# Sheet5.net
KiCad netlist of a schematic drawn in Altium Designer
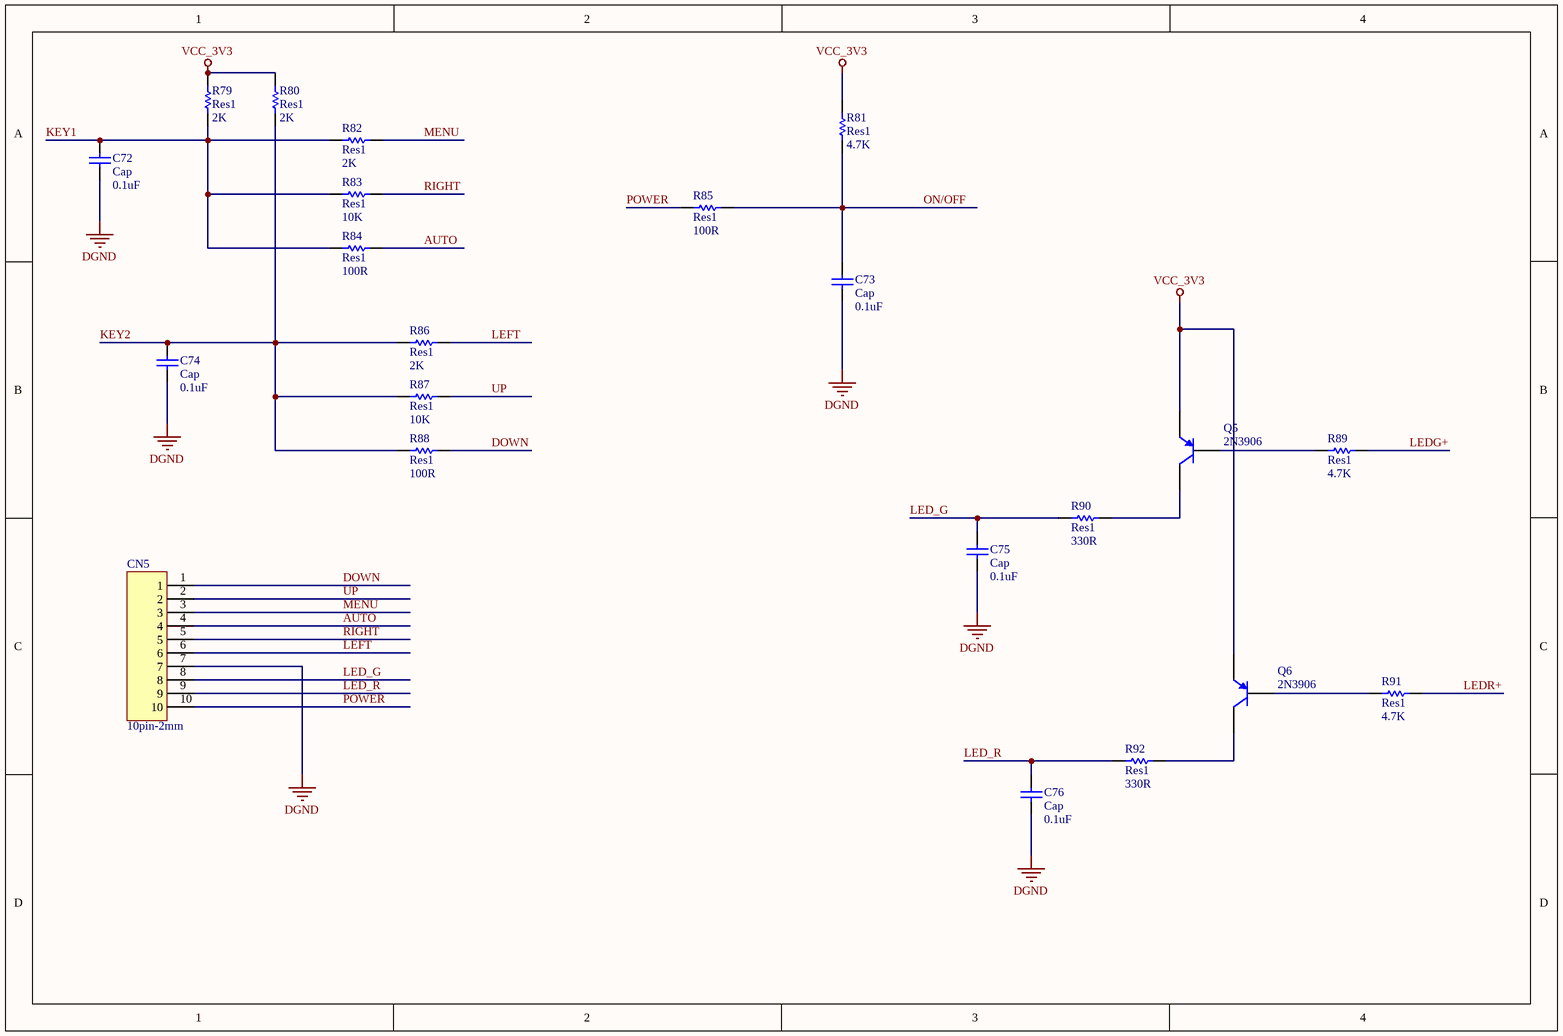
[diagram p0: Sheet5.SchDoc]

(export (version "E")
  (design (tool "Eeschema 10.0.6"))
  (components
    (comp (ref "C72")
      (value "Cap")
      (footprint "C-0402")
      (description "Capacitor")
      (fields (field (name "ALTIUM_VALUE") "0.1uF") (field (name "PUBLISHER") "Altium Limited"))
      (libsource (lib "Miscellaneous Devices") (part "Cap"))
    )
    (comp (ref "C73")
      (value "Cap")
      (footprint "C-0402")
      (description "Capacitor")
      (fields (field (name "ALTIUM_VALUE") "0.1uF") (field (name "PUBLISHER") "Altium Limited"))
      (libsource (lib "Miscellaneous Devices") (part "Cap"))
    )
    (comp (ref "C74")
      (value "Cap")
      (footprint "C-0402")
      (description "Capacitor")
      (fields (field (name "ALTIUM_VALUE") "0.1uF") (field (name "PUBLISHER") "Altium Limited"))
      (libsource (lib "Miscellaneous Devices") (part "Cap"))
    )
    (comp (ref "C75")
      (value "Cap")
      (footprint "C-0402")
      (description "Capacitor")
      (fields (field (name "ALTIUM_VALUE") "0.1uF") (field (name "PUBLISHER") "Altium Limited"))
      (libsource (lib "Miscellaneous Devices") (part "Cap"))
    )
    (comp (ref "C76")
      (value "Cap")
      (footprint "C-0402")
      (description "Capacitor")
      (fields (field (name "ALTIUM_VALUE") "0.1uF") (field (name "PUBLISHER") "Altium Limited"))
      (libsource (lib "Miscellaneous Devices") (part "Cap"))
    )
    (comp (ref "CN5") (value "10pin-2mm") (footprint "JP-10") (libsource (lib "SCHLIB") (part "10pin-2mm")))
    (comp (ref "Q5")
      (value "2N3906")
      (footprint "Q-SOT23")
      (description "PNP General Purpose Amplifier")
      (fields (field (name "PUBLISHER") "Altium Limited"))
      (libsource (lib "Miscellaneous Devices") (part "2N3906"))
    )
    (comp (ref "Q6")
      (value "2N3906")
      (footprint "Q-SOT23")
      (description "PNP General Purpose Amplifier")
      (fields (field (name "PUBLISHER") "Altium Limited"))
      (libsource (lib "Miscellaneous Devices") (part "2N3906"))
    )
    (comp (ref "R79")
      (value "Res1")
      (footprint "R-0603")
      (description "Resistor")
      (fields (field (name "ALTIUM_VALUE") "2K") (field (name "PUBLISHER") "Altium Limited"))
      (libsource (lib "Miscellaneous Devices") (part "Res1"))
    )
    (comp (ref "R80")
      (value "Res1")
      (footprint "R-0603")
      (description "Resistor")
      (fields (field (name "ALTIUM_VALUE") "2K") (field (name "PUBLISHER") "Altium Limited"))
      (libsource (lib "Miscellaneous Devices") (part "Res1"))
    )
    (comp (ref "R81")
      (value "Res1")
      (footprint "R-0603")
      (description "Resistor")
      (fields (field (name "ALTIUM_VALUE") "4.7K") (field (name "PUBLISHER") "Altium Limited"))
      (libsource (lib "Miscellaneous Devices") (part "Res1"))
    )
    (comp (ref "R82")
      (value "Res1")
      (footprint "R-0603")
      (description "Resistor")
      (fields (field (name "ALTIUM_VALUE") "2K") (field (name "PUBLISHER") "Altium Limited"))
      (libsource (lib "Miscellaneous Devices") (part "Res1"))
    )
    (comp (ref "R83")
      (value "Res1")
      (footprint "R-0603")
      (description "Resistor")
      (fields (field (name "ALTIUM_VALUE") "10K") (field (name "PUBLISHER") "Altium Limited"))
      (libsource (lib "Miscellaneous Devices") (part "Res1"))
    )
    (comp (ref "R84")
      (value "Res1")
      (footprint "R-0603")
      (description "Resistor")
      (fields (field (name "ALTIUM_VALUE") "100R") (field (name "PUBLISHER") "Altium Limited"))
      (libsource (lib "Miscellaneous Devices") (part "Res1"))
    )
    (comp (ref "R85")
      (value "Res1")
      (footprint "R-0603")
      (description "Resistor")
      (fields (field (name "ALTIUM_VALUE") "100R") (field (name "PUBLISHER") "Altium Limited"))
      (libsource (lib "Miscellaneous Devices") (part "Res1"))
    )
    (comp (ref "R86")
      (value "Res1")
      (footprint "R-0603")
      (description "Resistor")
      (fields (field (name "ALTIUM_VALUE") "2K") (field (name "PUBLISHER") "Altium Limited"))
      (libsource (lib "Miscellaneous Devices") (part "Res1"))
    )
    (comp (ref "R87")
      (value "Res1")
      (footprint "R-0603")
      (description "Resistor")
      (fields (field (name "ALTIUM_VALUE") "10K") (field (name "PUBLISHER") "Altium Limited"))
      (libsource (lib "Miscellaneous Devices") (part "Res1"))
    )
    (comp (ref "R88")
      (value "Res1")
      (footprint "R-0603")
      (description "Resistor")
      (fields (field (name "ALTIUM_VALUE") "100R") (field (name "PUBLISHER") "Altium Limited"))
      (libsource (lib "Miscellaneous Devices") (part "Res1"))
    )
    (comp (ref "R89")
      (value "Res1")
      (footprint "R-0603")
      (description "Resistor")
      (fields (field (name "ALTIUM_VALUE") "4.7K") (field (name "PUBLISHER") "Altium Limited"))
      (libsource (lib "Miscellaneous Devices") (part "Res1"))
    )
    (comp (ref "R90")
      (value "Res1")
      (footprint "R-0603")
      (description "Resistor")
      (fields (field (name "ALTIUM_VALUE") "330R") (field (name "PUBLISHER") "Altium Limited"))
      (libsource (lib "Miscellaneous Devices") (part "Res1"))
    )
    (comp (ref "R91")
      (value "Res1")
      (footprint "R-0603")
      (description "Resistor")
      (fields (field (name "ALTIUM_VALUE") "4.7K") (field (name "PUBLISHER") "Altium Limited"))
      (libsource (lib "Miscellaneous Devices") (part "Res1"))
    )
    (comp (ref "R92")
      (value "Res1")
      (footprint "R-0603")
      (description "Resistor")
      (fields (field (name "ALTIUM_VALUE") "330R") (field (name "PUBLISHER") "Altium Limited"))
      (libsource (lib "Miscellaneous Devices") (part "Res1"))
    )
  )
  (nets
    (net (code "1") (name "/AUTO") (class "Default")
      (node (ref "CN5") (pin "4") (pinfunction "4_4") (pintype "passive"))
      (node (ref "R84") (pin "1") (pinfunction "1_1") (pintype "passive"))
    )
    (net (code "2") (name "/DOWN") (class "Default")
      (node (ref "CN5") (pin "1") (pinfunction "1_1") (pintype "passive"))
      (node (ref "R88") (pin "1") (pinfunction "1_1") (pintype "passive"))
    )
    (net (code "3") (name "/KEY1") (class "Default")
      (node (ref "C72") (pin "2") (pinfunction "2_2") (pintype "passive"))
      (node (ref "R79") (pin "1") (pinfunction "1_1") (pintype "passive"))
      (node (ref "R82") (pin "2") (pinfunction "2_2") (pintype "passive"))
      (node (ref "R83") (pin "2") (pinfunction "2_2") (pintype "passive"))
      (node (ref "R84") (pin "2") (pinfunction "2_2") (pintype "passive"))
    )
    (net (code "4") (name "/KEY2") (class "Default")
      (node (ref "C74") (pin "2") (pinfunction "2_2") (pintype "passive"))
      (node (ref "R80") (pin "1") (pinfunction "1_1") (pintype "passive"))
      (node (ref "R86") (pin "2") (pinfunction "2_2") (pintype "passive"))
      (node (ref "R87") (pin "2") (pinfunction "2_2") (pintype "passive"))
      (node (ref "R88") (pin "2") (pinfunction "2_2") (pintype "passive"))
    )
    (net (code "5") (name "/LEDG+") (class "Default")
      (node (ref "R89") (pin "2") (pinfunction "2_2") (pintype "passive"))
    )
    (net (code "6") (name "/LEDR+") (class "Default")
      (node (ref "R91") (pin "2") (pinfunction "2_2") (pintype "passive"))
    )
    (net (code "7") (name "/LED_G") (class "Default")
      (node (ref "C75") (pin "2") (pinfunction "2_2") (pintype "passive"))
      (node (ref "CN5") (pin "8") (pinfunction "8_8") (pintype "passive"))
      (node (ref "R90") (pin "1") (pinfunction "1_1") (pintype "passive"))
    )
    (net (code "8") (name "/LED_R") (class "Default")
      (node (ref "C76") (pin "2") (pinfunction "2_2") (pintype "passive"))
      (node (ref "CN5") (pin "9") (pinfunction "9_9") (pintype "passive"))
      (node (ref "R92") (pin "1") (pinfunction "1_1") (pintype "passive"))
    )
    (net (code "9") (name "/LEFT") (class "Default")
      (node (ref "CN5") (pin "6") (pinfunction "6_6") (pintype "passive"))
      (node (ref "R86") (pin "1") (pinfunction "1_1") (pintype "passive"))
    )
    (net (code "10") (name "/MENU") (class "Default")
      (node (ref "CN5") (pin "3") (pinfunction "3_3") (pintype "passive"))
      (node (ref "R82") (pin "1") (pinfunction "1_1") (pintype "passive"))
    )
    (net (code "11") (name "/ON{slash}OFF") (class "Default")
      (node (ref "C73") (pin "2") (pinfunction "2_2") (pintype "passive"))
      (node (ref "R81") (pin "2") (pinfunction "2_2") (pintype "passive"))
      (node (ref "R85") (pin "1") (pinfunction "1_1") (pintype "passive"))
    )
    (net (code "12") (name "/POWER") (class "Default")
      (node (ref "CN5") (pin "10") (pinfunction "10_10") (pintype "passive"))
      (node (ref "R85") (pin "2") (pinfunction "2_2") (pintype "passive"))
    )
    (net (code "13") (name "/RIGHT") (class "Default")
      (node (ref "CN5") (pin "5") (pinfunction "5_5") (pintype "passive"))
      (node (ref "R83") (pin "1") (pinfunction "1_1") (pintype "passive"))
    )
    (net (code "14") (name "/UP") (class "Default")
      (node (ref "CN5") (pin "2") (pinfunction "2_2") (pintype "passive"))
      (node (ref "R87") (pin "1") (pinfunction "1_1") (pintype "passive"))
    )
    (net (code "15") (name "DGND") (class "Default")
      (node (ref "C72") (pin "1") (pinfunction "1_1") (pintype "passive"))
      (node (ref "C73") (pin "1") (pinfunction "1_1") (pintype "passive"))
      (node (ref "C74") (pin "1") (pinfunction "1_1") (pintype "passive"))
      (node (ref "C75") (pin "1") (pinfunction "1_1") (pintype "passive"))
      (node (ref "C76") (pin "1") (pinfunction "1_1") (pintype "passive"))
      (node (ref "CN5") (pin "7") (pinfunction "7_7") (pintype "passive"))
    )
    (net (code "16") (name "Net-(Q5-B)") (class "Default")
      (node (ref "Q5") (pin "2") (pinfunction "B_2") (pintype "passive"))
      (node (ref "R89") (pin "1") (pinfunction "1_1") (pintype "passive"))
    )
    (net (code "17") (name "Net-(Q5-C)") (class "Default")
      (node (ref "Q5") (pin "3") (pinfunction "C_3") (pintype "passive"))
      (node (ref "R90") (pin "2") (pinfunction "2_2") (pintype "passive"))
    )
    (net (code "18") (name "Net-(Q6-B)") (class "Default")
      (node (ref "Q6") (pin "2") (pinfunction "B_2") (pintype "passive"))
      (node (ref "R91") (pin "1") (pinfunction "1_1") (pintype "passive"))
    )
    (net (code "19") (name "Net-(Q6-C)") (class "Default")
      (node (ref "Q6") (pin "3") (pinfunction "C_3") (pintype "passive"))
      (node (ref "R92") (pin "2") (pinfunction "2_2") (pintype "passive"))
    )
    (net (code "20") (name "VCC_3V3") (class "Default")
      (node (ref "Q5") (pin "1") (pinfunction "E_1") (pintype "passive"))
      (node (ref "Q6") (pin "1") (pinfunction "E_1") (pintype "passive"))
      (node (ref "R79") (pin "2") (pinfunction "2_2") (pintype "passive"))
      (node (ref "R80") (pin "2") (pinfunction "2_2") (pintype "passive"))
      (node (ref "R81") (pin "1") (pinfunction "1_1") (pintype "passive"))
    )
  )
)
